# Arduino-DIP.net
KiCad netlist of a schematic drawn in EAGLE
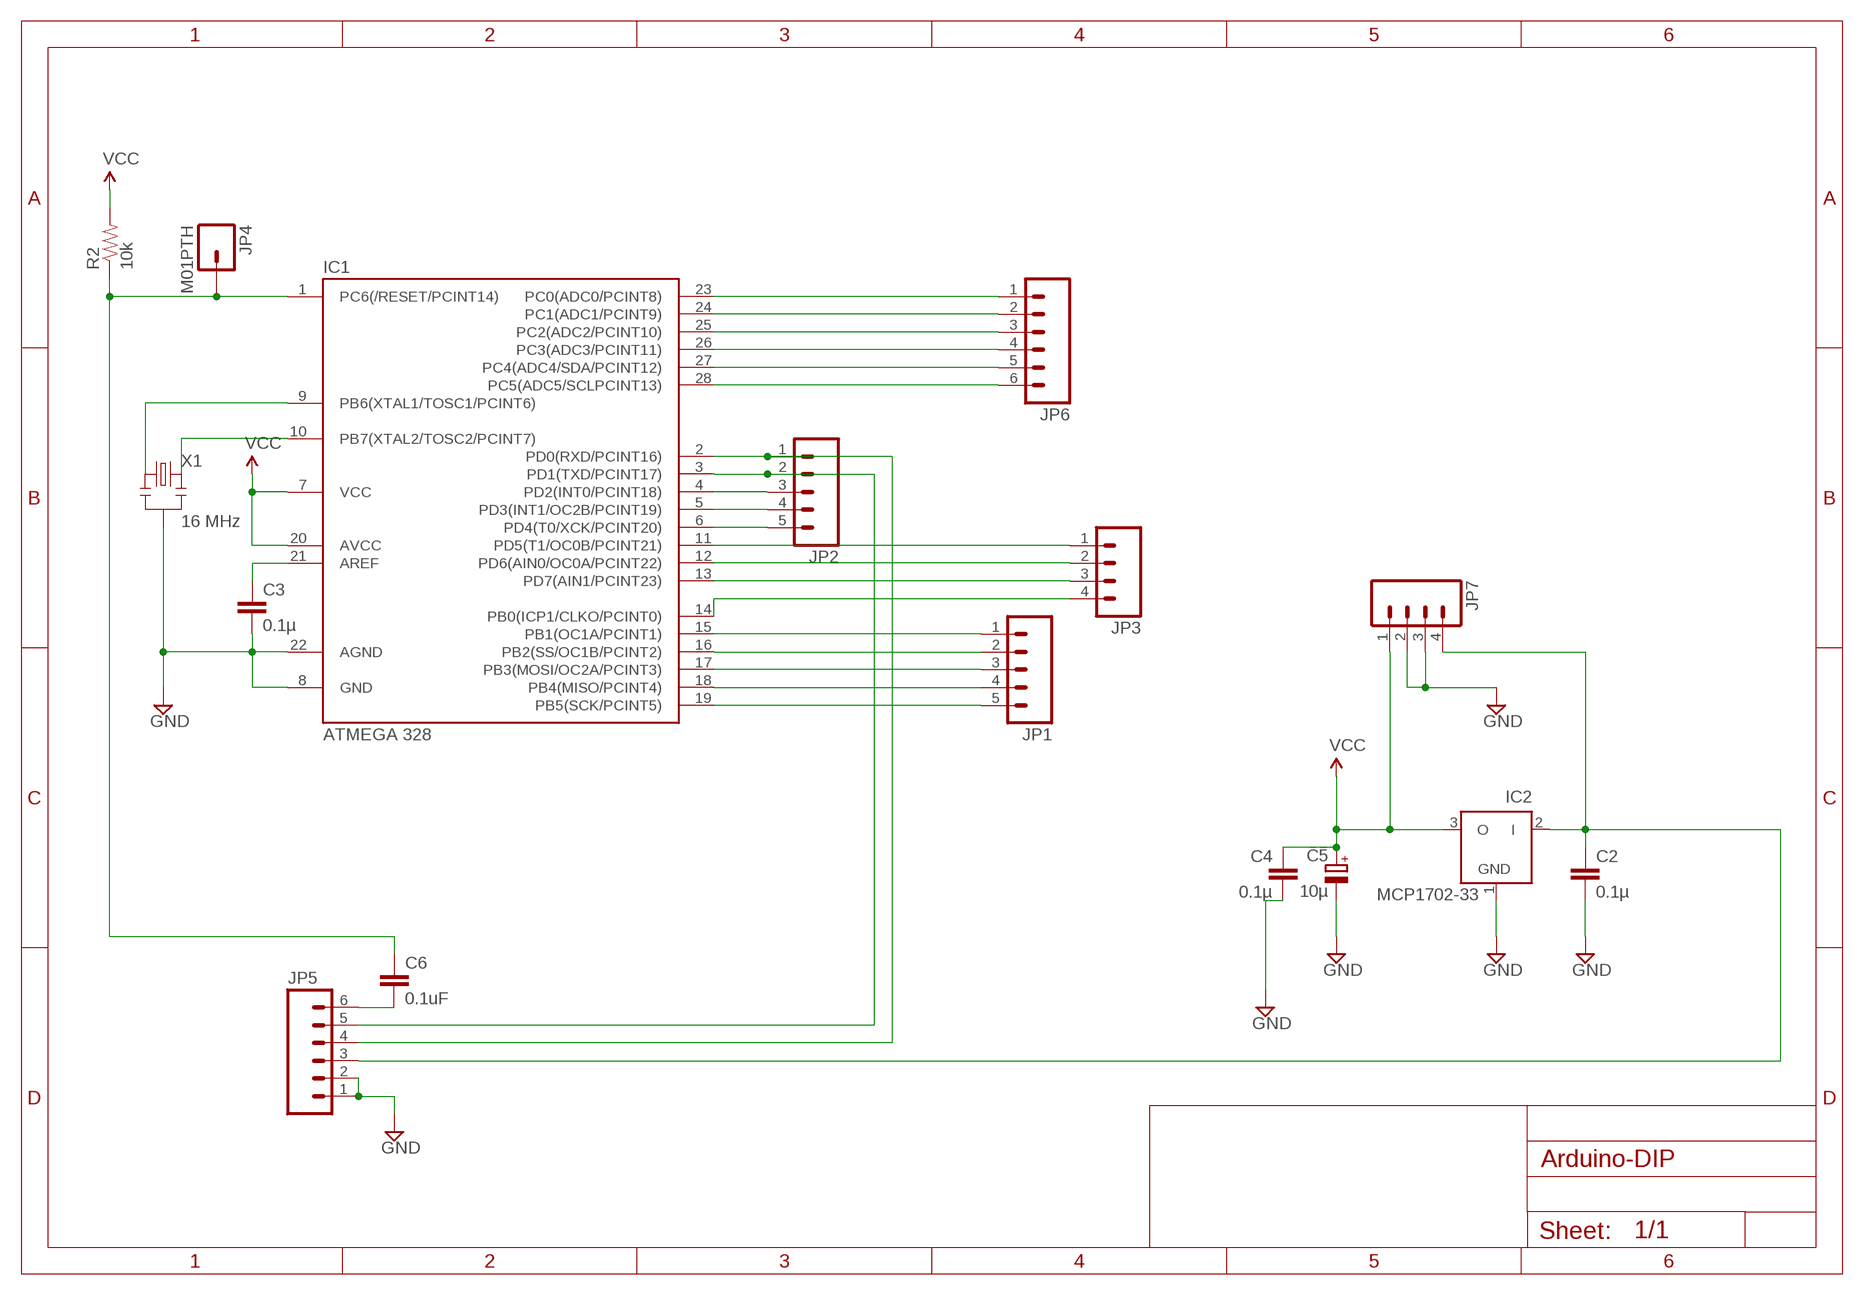
[diagram p0: schematic, sheet 1]

(export (version "E")
  (design (tool "Eeschema 10.0.6"))
  (components
    (comp (ref "C2")
      (value "0.1µ")
      (footprint "eagle-import:C025-024X044")
      (libsource (lib "eagle-import") (part "C-EU025-024X044"))
    )
    (comp (ref "C3")
      (value "0.1µ")
      (footprint "eagle-import:C025-024X044")
      (libsource (lib "eagle-import") (part "C-EU025-024X044"))
    )
    (comp (ref "C4")
      (value "0.1µ")
      (footprint "eagle-import:C025-024X044")
      (libsource (lib "eagle-import") (part "C-EU025-024X044"))
    )
    (comp (ref "C5")
      (value "10µ")
      (footprint "eagle-import:E1,8-4")
      (libsource (lib "eagle-import") (part "CPOL-EUE1.8-4"))
    )
    (comp (ref "C6")
      (value "0.1uF")
      (footprint "eagle-import:CAP-PTH-5MM")
      (libsource (lib "eagle-import") (part "CAPPTH1"))
    )
    (comp (ref "IC1")
      (value "ATMEGA 328")
      (footprint "eagle-import:DIL28-3")
      (libsource (lib "eagle-import") (part "ATMEGA48/88/168-PU"))
    )
    (comp (ref "IC2")
      (value "MCP1702-33")
      (footprint "eagle-import:TO92")
      (libsource (lib "eagle-import") (part "MCP1702Z"))
    )
    (comp (ref "JP1")
      (value "M05PTH")
      (footprint "eagle-import:1X05")
      (libsource (lib "eagle-import") (part "M05PTH"))
    )
    (comp (ref "JP2")
      (value "M05PTH")
      (footprint "eagle-import:1X05")
      (libsource (lib "eagle-import") (part "M05PTH"))
    )
    (comp (ref "JP3")
      (value "M04PTH")
      (footprint "eagle-import:1X04")
      (libsource (lib "eagle-import") (part "M04PTH"))
    )
    (comp (ref "JP4")
      (value "M01PTH")
      (footprint "eagle-import:1X01")
      (libsource (lib "eagle-import") (part "M01PTH"))
    )
    (comp (ref "JP5")
      (value "M06NO_SILK")
      (footprint "eagle-import:1X06_NO_SILK")
      (libsource (lib "eagle-import") (part "M06NO_SILK"))
    )
    (comp (ref "JP6")
      (value "M06NO_SILK")
      (footprint "eagle-import:1X06_NO_SILK")
      (libsource (lib "eagle-import") (part "M06NO_SILK"))
    )
    (comp (ref "JP7")
      (value "M04PTH")
      (footprint "eagle-import:1X04")
      (libsource (lib "eagle-import") (part "M04PTH"))
    )
    (comp (ref "R2")
      (value "10k")
      (footprint "eagle-import:1_6W-RES")
      (libsource (lib "eagle-import") (part "RESISTORPTH-1/6W"))
    )
    (comp (ref "X1")
      (value "16 MHz")
      (footprint "eagle-import:RESONATOR-PTH")
      (libsource (lib "eagle-import") (part "RESONATORPTH"))
    )
  )
  (nets
    (net (code "1") (name "GND") (class "Default")
      (node (ref "C2") (pin "2") (pinfunction "2_2") (pintype "passive"))
      (node (ref "C3") (pin "2") (pinfunction "2_2") (pintype "passive"))
      (node (ref "C4") (pin "2") (pinfunction "2_2") (pintype "passive"))
      (node (ref "C5") (pin "-") (pinfunction "-_-") (pintype "passive"))
      (node (ref "IC1") (pin "22") (pinfunction "AGND_22") (pintype "power_in"))
      (node (ref "IC1") (pin "8") (pinfunction "GND_8") (pintype "power_in"))
      (node (ref "IC2") (pin "1") (pinfunction "GND_1") (pintype "power_in"))
      (node (ref "JP5") (pin "1") (pinfunction "1_1") (pintype "passive"))
      (node (ref "JP5") (pin "2") (pinfunction "2_2") (pintype "passive"))
      (node (ref "JP7") (pin "2") (pinfunction "2_2") (pintype "passive"))
      (node (ref "JP7") (pin "3") (pinfunction "3_3") (pintype "passive"))
      (node (ref "X1") (pin "2") (pinfunction "2_2") (pintype "passive"))
    )
    (net (code "2") (name "Net-(C6-Pad2)") (class "Default")
      (node (ref "C6") (pin "2") (pinfunction "2_2") (pintype "passive"))
      (node (ref "JP5") (pin "6") (pinfunction "6_6") (pintype "passive"))
    )
    (net (code "3") (name "Net-(IC1-AREF)") (class "Default")
      (node (ref "C3") (pin "1") (pinfunction "1_1") (pintype "passive"))
      (node (ref "IC1") (pin "21") (pinfunction "AREF_21") (pintype "passive"))
    )
    (net (code "4") (name "Net-(IC1-PB0(ICP1{slash}CLKO{slash}PCINT0))") (class "Default")
      (node (ref "IC1") (pin "14") (pinfunction "PB0(ICP1/CLKO/PCINT0)_14") (pintype "bidirectional"))
      (node (ref "JP3") (pin "4") (pinfunction "4_4") (pintype "passive"))
    )
    (net (code "5") (name "Net-(IC1-PB1(OC1A{slash}PCINT1))") (class "Default")
      (node (ref "IC1") (pin "15") (pinfunction "PB1(OC1A/PCINT1)_15") (pintype "bidirectional"))
      (node (ref "JP1") (pin "1") (pinfunction "1_1") (pintype "passive"))
    )
    (net (code "6") (name "Net-(IC1-PB2(SS{slash}OC1B{slash}PCINT2))") (class "Default")
      (node (ref "IC1") (pin "16") (pinfunction "PB2(SS/OC1B/PCINT2)_16") (pintype "bidirectional"))
      (node (ref "JP1") (pin "2") (pinfunction "2_2") (pintype "passive"))
    )
    (net (code "7") (name "Net-(IC1-PB3(MOSI{slash}OC2A{slash}PCINT3))") (class "Default")
      (node (ref "IC1") (pin "17") (pinfunction "PB3(MOSI/OC2A/PCINT3)_17") (pintype "bidirectional"))
      (node (ref "JP1") (pin "3") (pinfunction "3_3") (pintype "passive"))
    )
    (net (code "8") (name "Net-(IC1-PB4(MISO{slash}PCINT4))") (class "Default")
      (node (ref "IC1") (pin "18") (pinfunction "PB4(MISO/PCINT4)_18") (pintype "bidirectional"))
      (node (ref "JP1") (pin "4") (pinfunction "4_4") (pintype "passive"))
    )
    (net (code "9") (name "Net-(IC1-PB5(SCK{slash}PCINT5))") (class "Default")
      (node (ref "IC1") (pin "19") (pinfunction "PB5(SCK/PCINT5)_19") (pintype "bidirectional"))
      (node (ref "JP1") (pin "5") (pinfunction "5_5") (pintype "passive"))
    )
    (net (code "10") (name "Net-(IC1-PB6(XTAL1{slash}TOSC1{slash}PCINT6))") (class "Default")
      (node (ref "IC1") (pin "9") (pinfunction "PB6(XTAL1/TOSC1/PCINT6)_9") (pintype "bidirectional"))
      (node (ref "X1") (pin "1") (pinfunction "1_1") (pintype "passive"))
    )
    (net (code "11") (name "Net-(IC1-PB7(XTAL2{slash}TOSC2{slash}PCINT7))") (class "Default")
      (node (ref "IC1") (pin "10") (pinfunction "PB7(XTAL2/TOSC2/PCINT7)_10") (pintype "bidirectional"))
      (node (ref "X1") (pin "3") (pinfunction "3_3") (pintype "passive"))
    )
    (net (code "12") (name "Net-(IC1-PC0(ADC0{slash}PCINT8))") (class "Default")
      (node (ref "IC1") (pin "23") (pinfunction "PC0(ADC0/PCINT8)_23") (pintype "bidirectional"))
      (node (ref "JP6") (pin "1") (pinfunction "1_1") (pintype "passive"))
    )
    (net (code "13") (name "Net-(IC1-PC1(ADC1{slash}PCINT9))") (class "Default")
      (node (ref "IC1") (pin "24") (pinfunction "PC1(ADC1/PCINT9)_24") (pintype "bidirectional"))
      (node (ref "JP6") (pin "2") (pinfunction "2_2") (pintype "passive"))
    )
    (net (code "14") (name "Net-(IC1-PC2(ADC2{slash}PCINT10))") (class "Default")
      (node (ref "IC1") (pin "25") (pinfunction "PC2(ADC2/PCINT10)_25") (pintype "bidirectional"))
      (node (ref "JP6") (pin "3") (pinfunction "3_3") (pintype "passive"))
    )
    (net (code "15") (name "Net-(IC1-PC3(ADC3{slash}PCINT11))") (class "Default")
      (node (ref "IC1") (pin "26") (pinfunction "PC3(ADC3/PCINT11)_26") (pintype "bidirectional"))
      (node (ref "JP6") (pin "4") (pinfunction "4_4") (pintype "passive"))
    )
    (net (code "16") (name "Net-(IC1-PC4(ADC4{slash}SDA{slash}PCINT12))") (class "Default")
      (node (ref "IC1") (pin "27") (pinfunction "PC4(ADC4/SDA/PCINT12)_27") (pintype "bidirectional"))
      (node (ref "JP6") (pin "5") (pinfunction "5_5") (pintype "passive"))
    )
    (net (code "17") (name "Net-(IC1-PC5(ADC5{slash}SCLPCINT13))") (class "Default")
      (node (ref "IC1") (pin "28") (pinfunction "PC5(ADC5/SCLPCINT13)_28") (pintype "bidirectional"))
      (node (ref "JP6") (pin "6") (pinfunction "6_6") (pintype "passive"))
    )
    (net (code "18") (name "Net-(IC1-PC6({slash}RESET{slash}PCINT14))") (class "Default")
      (node (ref "C6") (pin "1") (pinfunction "1_1") (pintype "passive"))
      (node (ref "IC1") (pin "1") (pinfunction "PC6(/RESET/PCINT14)_1") (pintype "bidirectional"))
      (node (ref "JP4") (pin "1") (pinfunction "1_1") (pintype "passive"))
      (node (ref "R2") (pin "1") (pinfunction "1_1") (pintype "passive"))
    )
    (net (code "19") (name "Net-(IC1-PD0(RXD{slash}PCINT16))") (class "Default")
      (node (ref "IC1") (pin "2") (pinfunction "PD0(RXD/PCINT16)_2") (pintype "bidirectional"))
      (node (ref "JP2") (pin "1") (pinfunction "1_1") (pintype "passive"))
      (node (ref "JP5") (pin "4") (pinfunction "4_4") (pintype "passive"))
    )
    (net (code "20") (name "Net-(IC1-PD1(TXD{slash}PCINT17))") (class "Default")
      (node (ref "IC1") (pin "3") (pinfunction "PD1(TXD/PCINT17)_3") (pintype "bidirectional"))
      (node (ref "JP2") (pin "2") (pinfunction "2_2") (pintype "passive"))
      (node (ref "JP5") (pin "5") (pinfunction "5_5") (pintype "passive"))
    )
    (net (code "21") (name "Net-(IC1-PD2(INT0{slash}PCINT18))") (class "Default")
      (node (ref "IC1") (pin "4") (pinfunction "PD2(INT0/PCINT18)_4") (pintype "bidirectional"))
      (node (ref "JP2") (pin "3") (pinfunction "3_3") (pintype "passive"))
    )
    (net (code "22") (name "Net-(IC1-PD3(INT1{slash}OC2B{slash}PCINT19))") (class "Default")
      (node (ref "IC1") (pin "5") (pinfunction "PD3(INT1/OC2B/PCINT19)_5") (pintype "bidirectional"))
      (node (ref "JP2") (pin "4") (pinfunction "4_4") (pintype "passive"))
    )
    (net (code "23") (name "Net-(IC1-PD4(T0{slash}XCK{slash}PCINT20))") (class "Default")
      (node (ref "IC1") (pin "6") (pinfunction "PD4(T0/XCK/PCINT20)_6") (pintype "bidirectional"))
      (node (ref "JP2") (pin "5") (pinfunction "5_5") (pintype "passive"))
    )
    (net (code "24") (name "Net-(IC1-PD5(T1{slash}OC0B{slash}PCINT21))") (class "Default")
      (node (ref "IC1") (pin "11") (pinfunction "PD5(T1/OC0B/PCINT21)_11") (pintype "bidirectional"))
      (node (ref "JP3") (pin "1") (pinfunction "1_1") (pintype "passive"))
    )
    (net (code "25") (name "Net-(IC1-PD6(AIN0{slash}OC0A{slash}PCINT22))") (class "Default")
      (node (ref "IC1") (pin "12") (pinfunction "PD6(AIN0/OC0A/PCINT22)_12") (pintype "bidirectional"))
      (node (ref "JP3") (pin "2") (pinfunction "2_2") (pintype "passive"))
    )
    (net (code "26") (name "Net-(IC1-PD7(AIN1{slash}PCINT23))") (class "Default")
      (node (ref "IC1") (pin "13") (pinfunction "PD7(AIN1/PCINT23)_13") (pintype "bidirectional"))
      (node (ref "JP3") (pin "3") (pinfunction "3_3") (pintype "passive"))
    )
    (net (code "27") (name "Net-(IC2-I)") (class "Default")
      (node (ref "C2") (pin "1") (pinfunction "1_1") (pintype "passive"))
      (node (ref "IC2") (pin "2") (pinfunction "I_2") (pintype "input"))
      (node (ref "JP5") (pin "3") (pinfunction "3_3") (pintype "passive"))
      (node (ref "JP7") (pin "4") (pinfunction "4_4") (pintype "passive"))
    )
    (net (code "28") (name "VCC") (class "Default")
      (node (ref "C4") (pin "1") (pinfunction "1_1") (pintype "passive"))
      (node (ref "C5") (pin "+") (pinfunction "+_+") (pintype "passive"))
      (node (ref "IC1") (pin "20") (pinfunction "AVCC_20") (pintype "passive"))
      (node (ref "IC1") (pin "7") (pinfunction "VCC_7") (pintype "power_in"))
      (node (ref "IC2") (pin "3") (pinfunction "O_3") (pintype "input"))
      (node (ref "JP7") (pin "1") (pinfunction "1_1") (pintype "passive"))
      (node (ref "R2") (pin "2") (pinfunction "2_2") (pintype "passive"))
    )
  )
)
